# ATmega_Sesnos_Controller.net
KiCad netlist of a schematic drawn in EAGLE
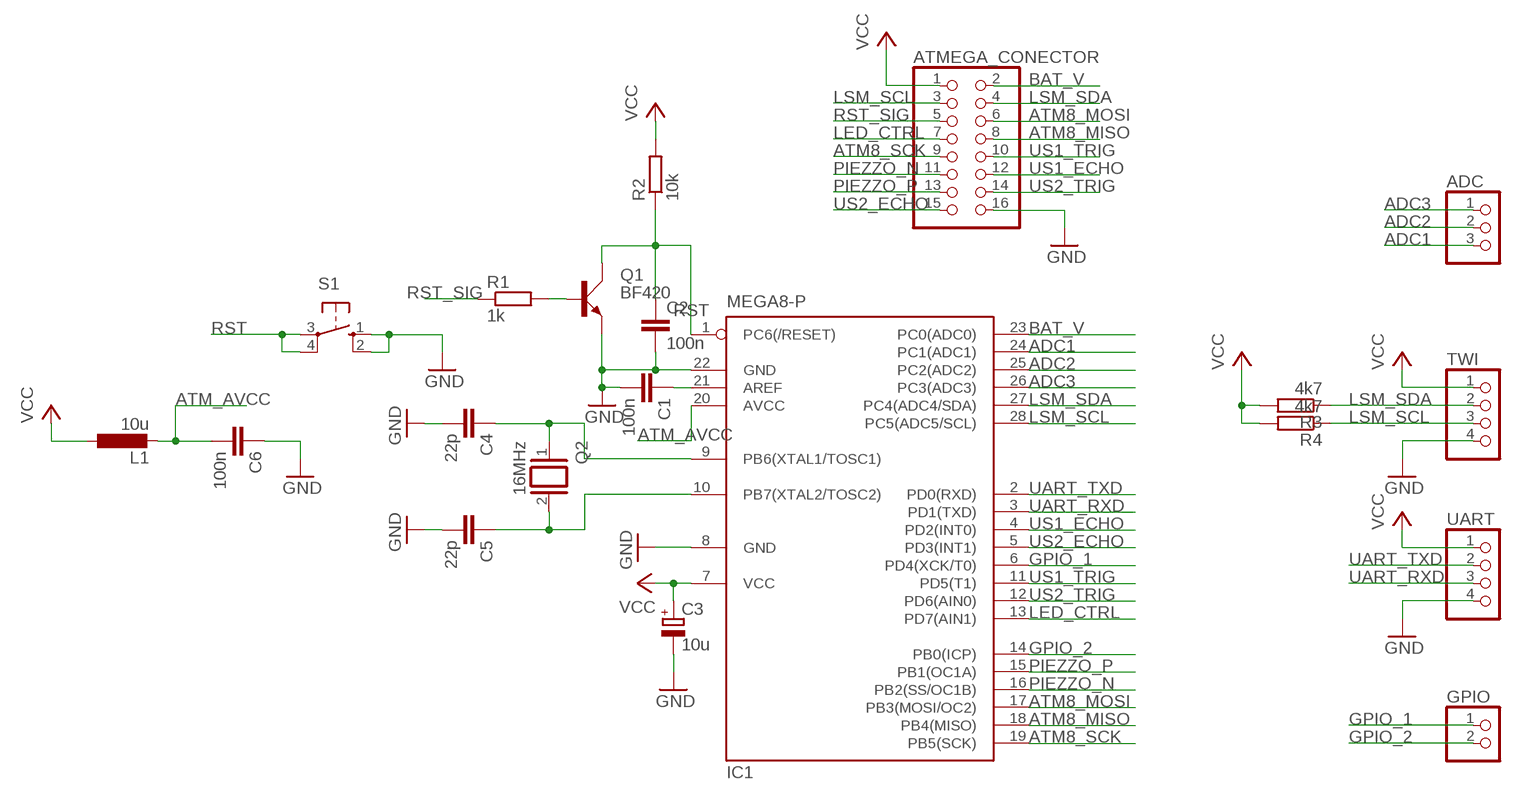
[diagram p0: schematic, sheet 1]

(export (version "E")
  (design (tool "Eeschema 10.0.6"))
  (components
    (comp (ref "ADC")
      (value "PINHD-1X3/90")
      (footprint "eagle-import:1X03_90")
      (libsource (lib "eagle-import") (part "PINHD-1X3/90"))
    )
    (comp (ref "ATMEGA_CONECTOR")
      (value "PINHD-2X8")
      (footprint "eagle-import:2X08")
      (libsource (lib "eagle-import") (part "PINHD-2X8"))
    )
    (comp (ref "C1")
      (value "100n")
      (footprint "eagle-import:C025-024X044")
      (libsource (lib "eagle-import") (part "C-EU025-024X044"))
    )
    (comp (ref "C2")
      (value "100n")
      (footprint "eagle-import:C025-024X044")
      (libsource (lib "eagle-import") (part "C-EU025-024X044"))
    )
    (comp (ref "C3")
      (value "10u")
      (footprint "eagle-import:E5-5")
      (libsource (lib "eagle-import") (part "CPOL-EUE5-5"))
    )
    (comp (ref "C4")
      (value "22p")
      (footprint "eagle-import:C025-024X044")
      (libsource (lib "eagle-import") (part "C-EU025-024X044"))
    )
    (comp (ref "C5")
      (value "22p")
      (footprint "eagle-import:C025-024X044")
      (libsource (lib "eagle-import") (part "C-EU025-024X044"))
    )
    (comp (ref "C6")
      (value "100n")
      (footprint "eagle-import:C025-024X044")
      (libsource (lib "eagle-import") (part "C-EU025-024X044"))
    )
    (comp (ref "GPIO")
      (value "PINHD-1X2/90")
      (footprint "eagle-import:1X02_90")
      (libsource (lib "eagle-import") (part "PINHD-1X2/90"))
    )
    (comp (ref "IC1")
      (value "MEGA8-P")
      (footprint "eagle-import:DIL28-3")
      (libsource (lib "eagle-import") (part "MEGA8-P"))
    )
    (comp (ref "L1")
      (value "10u")
      (footprint "eagle-import:0204_7")
      (libsource (lib "eagle-import") (part "L-EU0204/7"))
    )
    (comp (ref "Q1")
      (value "BF420")
      (footprint "eagle-import:SOT54D")
      (libsource (lib "eagle-import") (part "BF420"))
    )
    (comp (ref "Q2")
      (value "16MHz")
      (footprint "eagle-import:QS")
      (libsource (lib "eagle-import") (part "XTAL/S"))
    )
    (comp (ref "R1")
      (value "1k")
      (footprint "eagle-import:0309_10")
      (libsource (lib "eagle-import") (part "R-EU_0309/10"))
    )
    (comp (ref "R2")
      (value "10k")
      (footprint "eagle-import:0309_10")
      (libsource (lib "eagle-import") (part "R-EU_0309/10"))
    )
    (comp (ref "R3")
      (value "4k7")
      (footprint "eagle-import:0204_5")
      (libsource (lib "eagle-import") (part "R-EU_0204/5"))
    )
    (comp (ref "R4")
      (value "4k7")
      (footprint "eagle-import:0204_5")
      (libsource (lib "eagle-import") (part "R-EU_0204/5"))
    )
    (comp (ref "S1")
      (value "10-XX")
      (footprint "eagle-import:B3F-10XX")
      (fields (field (name "MPN") "B3F-1000"))
      (libsource (lib "eagle-import") (part "10-XX"))
    )
    (comp (ref "TWI")
      (value "PINHD-1X4/90")
      (footprint "eagle-import:1X04_90")
      (libsource (lib "eagle-import") (part "PINHD-1X4/90"))
    )
    (comp (ref "UART")
      (value "PINHD-1X4/90")
      (footprint "eagle-import:1X04_90")
      (libsource (lib "eagle-import") (part "PINHD-1X4/90"))
    )
  )
  (nets
    (net (code "1") (name "/ADC1") (class "Default")
      (node (ref "ADC") (pin "3") (pinfunction "3_3") (pintype "passive"))
      (node (ref "IC1") (pin "24") (pinfunction "PC1(ADC1)_24") (pintype "bidirectional"))
    )
    (net (code "2") (name "/ADC2") (class "Default")
      (node (ref "ADC") (pin "2") (pinfunction "2_2") (pintype "passive"))
      (node (ref "IC1") (pin "25") (pinfunction "PC2(ADC2)_25") (pintype "bidirectional"))
    )
    (net (code "3") (name "/ADC3") (class "Default")
      (node (ref "ADC") (pin "1") (pinfunction "1_1") (pintype "passive"))
      (node (ref "IC1") (pin "26") (pinfunction "PC3(ADC3)_26") (pintype "bidirectional"))
    )
    (net (code "4") (name "/ATM8_MISO") (class "Default")
      (node (ref "ATMEGA_CONECTOR") (pin "8") (pinfunction "8_8") (pintype "passive"))
      (node (ref "IC1") (pin "18") (pinfunction "PB4(MISO)_18") (pintype "bidirectional"))
    )
    (net (code "5") (name "/ATM8_MOSI") (class "Default")
      (node (ref "ATMEGA_CONECTOR") (pin "6") (pinfunction "6_6") (pintype "passive"))
      (node (ref "IC1") (pin "17") (pinfunction "PB3(MOSI/OC2)_17") (pintype "bidirectional"))
    )
    (net (code "6") (name "/ATM8_SCK") (class "Default")
      (node (ref "ATMEGA_CONECTOR") (pin "9") (pinfunction "9_9") (pintype "passive"))
      (node (ref "IC1") (pin "19") (pinfunction "PB5(SCK)_19") (pintype "bidirectional"))
    )
    (net (code "7") (name "/ATM_AVCC") (class "Default")
      (node (ref "C6") (pin "2") (pinfunction "2_2") (pintype "passive"))
      (node (ref "IC1") (pin "20") (pinfunction "AVCC_20") (pintype "power_in"))
      (node (ref "L1") (pin "2") (pinfunction "2_2") (pintype "passive"))
    )
    (net (code "8") (name "/BAT_V") (class "Default")
      (node (ref "ATMEGA_CONECTOR") (pin "2") (pinfunction "2_2") (pintype "passive"))
      (node (ref "IC1") (pin "23") (pinfunction "PC0(ADC0)_23") (pintype "bidirectional"))
    )
    (net (code "9") (name "/GPIO_1") (class "Default")
      (node (ref "GPIO") (pin "1") (pinfunction "1_1") (pintype "passive"))
      (node (ref "IC1") (pin "6") (pinfunction "PD4(XCK/T0)_6") (pintype "bidirectional"))
    )
    (net (code "10") (name "/GPIO_2") (class "Default")
      (node (ref "GPIO") (pin "2") (pinfunction "2_2") (pintype "passive"))
      (node (ref "IC1") (pin "14") (pinfunction "PB0(ICP)_14") (pintype "bidirectional"))
    )
    (net (code "11") (name "/LED_CTRL") (class "Default")
      (node (ref "ATMEGA_CONECTOR") (pin "7") (pinfunction "7_7") (pintype "passive"))
      (node (ref "IC1") (pin "13") (pinfunction "PD7(AIN1)_13") (pintype "bidirectional"))
    )
    (net (code "12") (name "/LSM_SCL") (class "Default")
      (node (ref "ATMEGA_CONECTOR") (pin "3") (pinfunction "3_3") (pintype "passive"))
      (node (ref "IC1") (pin "28") (pinfunction "PC5(ADC5/SCL)_28") (pintype "bidirectional"))
      (node (ref "R4") (pin "1") (pinfunction "1_1") (pintype "passive"))
      (node (ref "TWI") (pin "3") (pinfunction "3_3") (pintype "passive"))
    )
    (net (code "13") (name "/LSM_SDA") (class "Default")
      (node (ref "ATMEGA_CONECTOR") (pin "4") (pinfunction "4_4") (pintype "passive"))
      (node (ref "IC1") (pin "27") (pinfunction "PC4(ADC4/SDA)_27") (pintype "bidirectional"))
      (node (ref "R3") (pin "1") (pinfunction "1_1") (pintype "passive"))
      (node (ref "TWI") (pin "2") (pinfunction "2_2") (pintype "passive"))
    )
    (net (code "14") (name "/PIEZZO_N") (class "Default")
      (node (ref "ATMEGA_CONECTOR") (pin "11") (pinfunction "11_11") (pintype "passive"))
      (node (ref "IC1") (pin "16") (pinfunction "PB2(SS/OC1B)_16") (pintype "bidirectional"))
    )
    (net (code "15") (name "/PIEZZO_P") (class "Default")
      (node (ref "ATMEGA_CONECTOR") (pin "13") (pinfunction "13_13") (pintype "passive"))
      (node (ref "IC1") (pin "15") (pinfunction "PB1(OC1A)_15") (pintype "bidirectional"))
    )
    (net (code "16") (name "/RST") (class "Default")
      (node (ref "C2") (pin "1") (pinfunction "1_1") (pintype "passive"))
      (node (ref "IC1") (pin "1") (pinfunction "PC6(/RESET)_1") (pintype "bidirectional"))
      (node (ref "Q1") (pin "C") (pinfunction "C_C") (pintype "passive"))
      (node (ref "R2") (pin "1") (pinfunction "1_1") (pintype "passive"))
      (node (ref "S1") (pin "3") (pinfunction "P_3") (pintype "passive"))
      (node (ref "S1") (pin "4") (pinfunction "P1_4") (pintype "passive"))
    )
    (net (code "17") (name "/RST_SIG") (class "Default")
      (node (ref "ATMEGA_CONECTOR") (pin "5") (pinfunction "5_5") (pintype "passive"))
      (node (ref "R1") (pin "1") (pinfunction "1_1") (pintype "passive"))
    )
    (net (code "18") (name "/UART_RXD") (class "Default")
      (node (ref "IC1") (pin "3") (pinfunction "PD1(TXD)_3") (pintype "bidirectional"))
      (node (ref "UART") (pin "3") (pinfunction "3_3") (pintype "passive"))
    )
    (net (code "19") (name "/UART_TXD") (class "Default")
      (node (ref "IC1") (pin "2") (pinfunction "PD0(RXD)_2") (pintype "bidirectional"))
      (node (ref "UART") (pin "2") (pinfunction "2_2") (pintype "passive"))
    )
    (net (code "20") (name "/US1_ECHO") (class "Default")
      (node (ref "ATMEGA_CONECTOR") (pin "12") (pinfunction "12_12") (pintype "passive"))
      (node (ref "IC1") (pin "4") (pinfunction "PD2(INT0)_4") (pintype "bidirectional"))
    )
    (net (code "21") (name "/US1_TRIG") (class "Default")
      (node (ref "ATMEGA_CONECTOR") (pin "10") (pinfunction "10_10") (pintype "passive"))
      (node (ref "IC1") (pin "11") (pinfunction "PD5(T1)_11") (pintype "bidirectional"))
    )
    (net (code "22") (name "/US2_ECHO") (class "Default")
      (node (ref "ATMEGA_CONECTOR") (pin "15") (pinfunction "15_15") (pintype "passive"))
      (node (ref "IC1") (pin "5") (pinfunction "PD3(INT1)_5") (pintype "bidirectional"))
    )
    (net (code "23") (name "/US2_TRIG") (class "Default")
      (node (ref "ATMEGA_CONECTOR") (pin "14") (pinfunction "14_14") (pintype "passive"))
      (node (ref "IC1") (pin "12") (pinfunction "PD6(AIN0)_12") (pintype "bidirectional"))
    )
    (net (code "24") (name "GND") (class "Default")
      (node (ref "ATMEGA_CONECTOR") (pin "16") (pinfunction "16_16") (pintype "passive"))
      (node (ref "C1") (pin "2") (pinfunction "2_2") (pintype "passive"))
      (node (ref "C2") (pin "2") (pinfunction "2_2") (pintype "passive"))
      (node (ref "C3") (pin "-") (pinfunction "-_-") (pintype "passive"))
      (node (ref "C4") (pin "2") (pinfunction "2_2") (pintype "passive"))
      (node (ref "C5") (pin "2") (pinfunction "2_2") (pintype "passive"))
      (node (ref "C6") (pin "1") (pinfunction "1_1") (pintype "passive"))
      (node (ref "IC1") (pin "22") (pinfunction "GND_22") (pintype "power_in"))
      (node (ref "IC1") (pin "8") (pinfunction "GND_8") (pintype "power_in"))
      (node (ref "Q1") (pin "E") (pinfunction "E_E") (pintype "passive"))
      (node (ref "S1") (pin "1") (pinfunction "S_1") (pintype "passive"))
      (node (ref "S1") (pin "2") (pinfunction "S1_2") (pintype "passive"))
      (node (ref "TWI") (pin "4") (pinfunction "4_4") (pintype "passive"))
      (node (ref "UART") (pin "4") (pinfunction "4_4") (pintype "passive"))
    )
    (net (code "25") (name "Net-(IC1-AREF)") (class "Default")
      (node (ref "C1") (pin "1") (pinfunction "1_1") (pintype "passive"))
      (node (ref "IC1") (pin "21") (pinfunction "AREF_21") (pintype "passive"))
    )
    (net (code "26") (name "Net-(IC1-PB6(XTAL1{slash}TOSC1))") (class "Default")
      (node (ref "C4") (pin "1") (pinfunction "1_1") (pintype "passive"))
      (node (ref "IC1") (pin "9") (pinfunction "PB6(XTAL1/TOSC1)_9") (pintype "bidirectional"))
      (node (ref "Q2") (pin "1") (pinfunction "1_1") (pintype "passive"))
    )
    (net (code "27") (name "Net-(IC1-PB7(XTAL2{slash}TOSC2))") (class "Default")
      (node (ref "C5") (pin "1") (pinfunction "1_1") (pintype "passive"))
      (node (ref "IC1") (pin "10") (pinfunction "PB7(XTAL2/TOSC2)_10") (pintype "bidirectional"))
      (node (ref "Q2") (pin "2") (pinfunction "2_2") (pintype "passive"))
    )
    (net (code "28") (name "Net-(Q1-PadB)") (class "Default")
      (node (ref "Q1") (pin "B") (pinfunction "B_B") (pintype "passive"))
      (node (ref "R1") (pin "2") (pinfunction "2_2") (pintype "passive"))
    )
    (net (code "29") (name "VCC") (class "Default")
      (node (ref "ATMEGA_CONECTOR") (pin "1") (pinfunction "1_1") (pintype "passive"))
      (node (ref "C3") (pin "+") (pinfunction "+_+") (pintype "passive"))
      (node (ref "IC1") (pin "7") (pinfunction "VCC_7") (pintype "power_in"))
      (node (ref "L1") (pin "1") (pinfunction "1_1") (pintype "passive"))
      (node (ref "R2") (pin "2") (pinfunction "2_2") (pintype "passive"))
      (node (ref "R3") (pin "2") (pinfunction "2_2") (pintype "passive"))
      (node (ref "R4") (pin "2") (pinfunction "2_2") (pintype "passive"))
      (node (ref "TWI") (pin "1") (pinfunction "1_1") (pintype "passive"))
      (node (ref "UART") (pin "1") (pinfunction "1_1") (pintype "passive"))
    )
  )
)
